# 14_-CURRENT_METER.net
KiCad netlist of a schematic drawn in Altium Designer
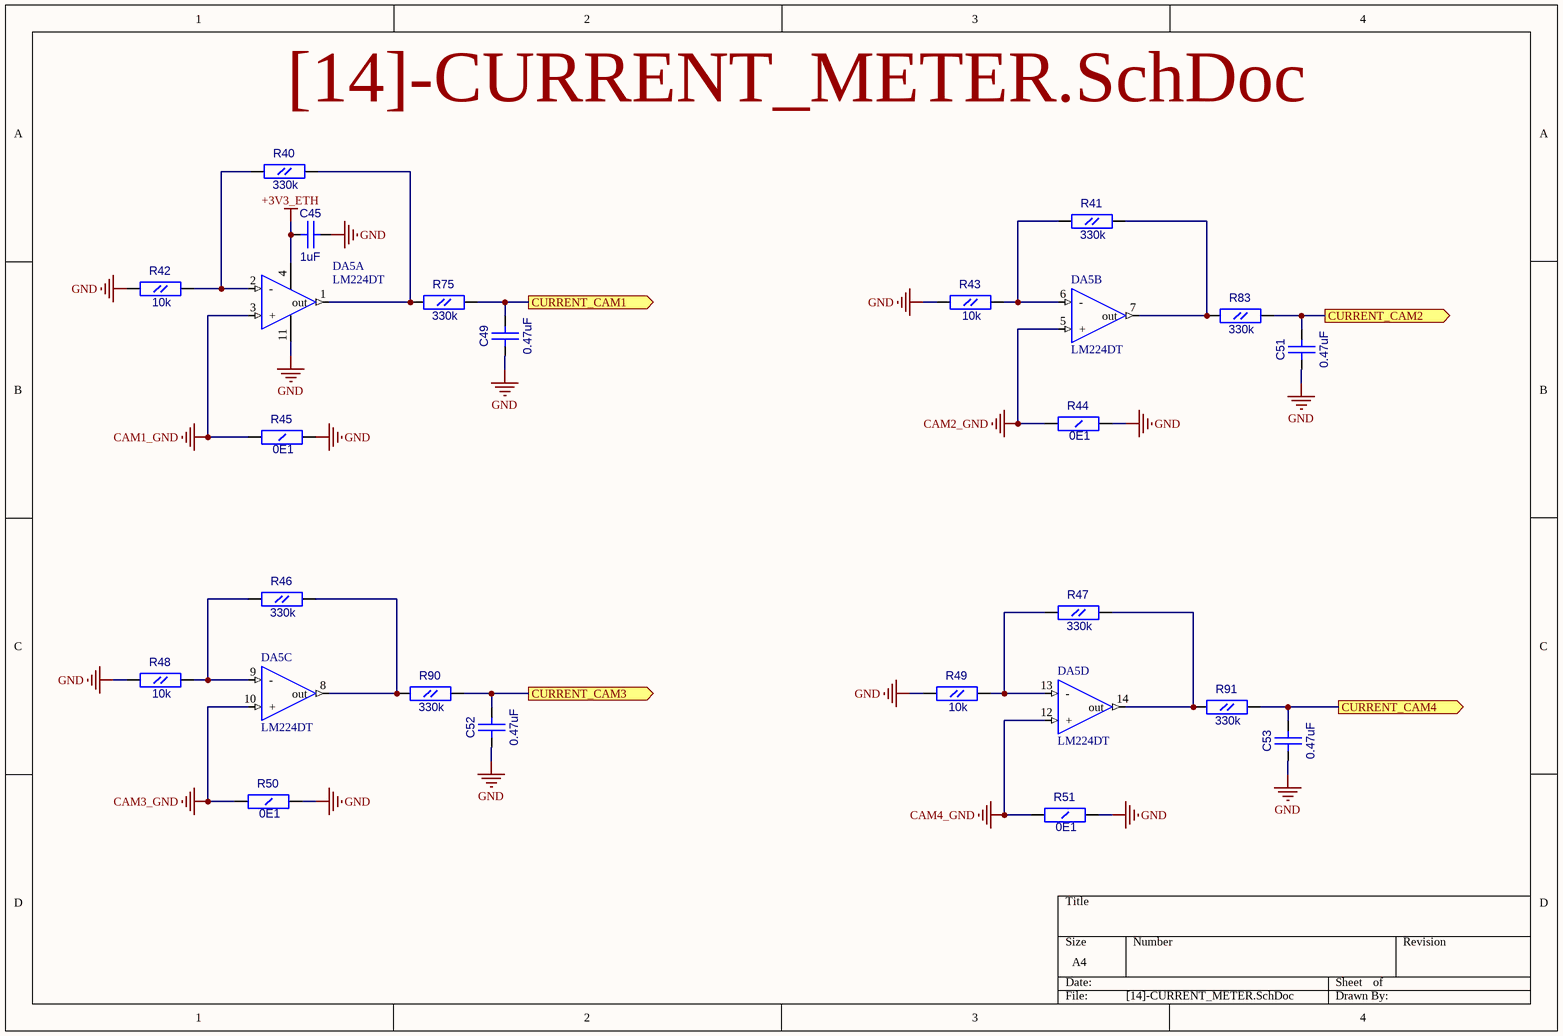
[diagram p0: [14]-CURRENT_METER.SchDoc]

(export (version "E")
  (design (tool "Eeschema 10.0.6"))
  (components
    (comp (ref "C45")
      (value "1uF")
      (footprint "CC0603")
      (description "CC0603")
      (libsource (lib "fizik_lib") (part "CC0603"))
    )
    (comp (ref "C49")
      (value "0.47uF")
      (footprint "CC0603")
      (description "CC0603")
      (libsource (lib "fizik_lib") (part "CC0603"))
    )
    (comp (ref "C51")
      (value "0.47uF")
      (footprint "CC0603")
      (description "CC0603")
      (libsource (lib "fizik_lib") (part "CC0603"))
    )
    (comp (ref "C52")
      (value "0.47uF")
      (footprint "CC0603")
      (description "CC0603")
      (libsource (lib "fizik_lib") (part "CC0603"))
    )
    (comp (ref "C53")
      (value "0.47uF")
      (footprint "CC0603")
      (description "CC0603")
      (libsource (lib "fizik_lib") (part "CC0603"))
    )
    (comp (ref "DA5") (value "LM224DT") (footprint "SO14") (libsource (lib "fizik_lib") (part "LM324D")))
    (comp (ref "R40")
      (value "330k")
      (footprint "RC0603")
      (description "RC0603")
      (libsource (lib "fizik_lib") (part "RC0603"))
    )
    (comp (ref "R41")
      (value "330k")
      (footprint "RC0603")
      (description "RC0603")
      (libsource (lib "fizik_lib") (part "RC0603"))
    )
    (comp (ref "R42")
      (value "10k")
      (footprint "RC0603")
      (description "RC0603")
      (libsource (lib "fizik_lib") (part "RC0603"))
    )
    (comp (ref "R43")
      (value "10k")
      (footprint "RC0603")
      (description "RC0603")
      (libsource (lib "fizik_lib") (part "RC0603"))
    )
    (comp (ref "R44")
      (value "0E1")
      (footprint "RC1206")
      (description "RC1206")
      (libsource (lib "fizik_lib (1)") (part "RC1206"))
    )
    (comp (ref "R45")
      (value "0E1")
      (footprint "RC1206")
      (description "RC1206")
      (libsource (lib "fizik_lib (1)") (part "RC1206"))
    )
    (comp (ref "R46")
      (value "330k")
      (footprint "RC0603")
      (description "RC0603")
      (libsource (lib "fizik_lib") (part "RC0603"))
    )
    (comp (ref "R47")
      (value "330k")
      (footprint "RC0603")
      (description "RC0603")
      (libsource (lib "fizik_lib") (part "RC0603"))
    )
    (comp (ref "R48")
      (value "10k")
      (footprint "RC0603")
      (description "RC0603")
      (libsource (lib "fizik_lib") (part "RC0603"))
    )
    (comp (ref "R49")
      (value "10k")
      (footprint "RC0603")
      (description "RC0603")
      (libsource (lib "fizik_lib") (part "RC0603"))
    )
    (comp (ref "R50")
      (value "0E1")
      (footprint "RC1206")
      (description "RC1206")
      (libsource (lib "fizik_lib (1)") (part "RC1206"))
    )
    (comp (ref "R51")
      (value "0E1")
      (footprint "RC1206")
      (description "RC1206")
      (libsource (lib "fizik_lib (1)") (part "RC1206"))
    )
    (comp (ref "R75")
      (value "330k")
      (footprint "RC0603")
      (description "RC0603")
      (libsource (lib "fizik_lib") (part "RC0603"))
    )
    (comp (ref "R83")
      (value "330k")
      (footprint "RC0603")
      (description "RC0603")
      (libsource (lib "fizik_lib") (part "RC0603"))
    )
    (comp (ref "R90")
      (value "330k")
      (footprint "RC0603")
      (description "RC0603")
      (libsource (lib "fizik_lib") (part "RC0603"))
    )
    (comp (ref "R91")
      (value "330k")
      (footprint "RC0603")
      (description "RC0603")
      (libsource (lib "fizik_lib") (part "RC0603"))
    )
  )
  (nets
    (net (code "1") (name "+3V3_ETH") (class "Default")
      (node (ref "C45") (pin "1") (pinfunction "A_1") (pintype "passive"))
      (node (ref "DA5") (pin "4") (pinfunction "V+_4") (pintype "passive"))
    )
    (net (code "2") (name "/CURRENT_CAM1") (class "Default")
      (node (ref "C49") (pin "2") (pinfunction "B_2") (pintype "passive"))
      (node (ref "R75") (pin "2") (pinfunction "B_2") (pintype "passive"))
    )
    (net (code "3") (name "/CURRENT_CAM2") (class "Default")
      (node (ref "C51") (pin "2") (pinfunction "B_2") (pintype "passive"))
      (node (ref "R83") (pin "2") (pinfunction "B_2") (pintype "passive"))
    )
    (net (code "4") (name "/CURRENT_CAM3") (class "Default")
      (node (ref "C52") (pin "2") (pinfunction "B_2") (pintype "passive"))
      (node (ref "R90") (pin "2") (pinfunction "B_2") (pintype "passive"))
    )
    (net (code "5") (name "/CURRENT_CAM4") (class "Default")
      (node (ref "C53") (pin "2") (pinfunction "B_2") (pintype "passive"))
      (node (ref "R91") (pin "2") (pinfunction "B_2") (pintype "passive"))
    )
    (net (code "6") (name "CAM1_GND") (class "Default")
      (node (ref "DA5") (pin "3") (pinfunction "+_3") (pintype "input"))
      (node (ref "R45") (pin "1") (pinfunction "A_1") (pintype "passive"))
    )
    (net (code "7") (name "CAM2_GND") (class "Default")
      (node (ref "DA5") (pin "5") (pinfunction "+_5") (pintype "input"))
      (node (ref "R44") (pin "1") (pinfunction "A_1") (pintype "passive"))
    )
    (net (code "8") (name "CAM3_GND") (class "Default")
      (node (ref "DA5") (pin "10") (pinfunction "+_10") (pintype "input"))
      (node (ref "R50") (pin "1") (pinfunction "A_1") (pintype "passive"))
    )
    (net (code "9") (name "CAM4_GND") (class "Default")
      (node (ref "DA5") (pin "12") (pinfunction "+_12") (pintype "input"))
      (node (ref "R51") (pin "1") (pinfunction "A_1") (pintype "passive"))
    )
    (net (code "10") (name "GND") (class "Default")
      (node (ref "C45") (pin "2") (pinfunction "B_2") (pintype "passive"))
      (node (ref "C49") (pin "1") (pinfunction "A_1") (pintype "passive"))
      (node (ref "C51") (pin "1") (pinfunction "A_1") (pintype "passive"))
      (node (ref "C52") (pin "1") (pinfunction "A_1") (pintype "passive"))
      (node (ref "C53") (pin "1") (pinfunction "A_1") (pintype "passive"))
      (node (ref "DA5") (pin "11") (pinfunction "V-_11") (pintype "passive"))
      (node (ref "R42") (pin "1") (pinfunction "A_1") (pintype "passive"))
      (node (ref "R43") (pin "1") (pinfunction "A_1") (pintype "passive"))
      (node (ref "R44") (pin "2") (pinfunction "B_2") (pintype "passive"))
      (node (ref "R45") (pin "2") (pinfunction "B_2") (pintype "passive"))
      (node (ref "R48") (pin "1") (pinfunction "A_1") (pintype "passive"))
      (node (ref "R49") (pin "1") (pinfunction "A_1") (pintype "passive"))
      (node (ref "R50") (pin "2") (pinfunction "B_2") (pintype "passive"))
      (node (ref "R51") (pin "2") (pinfunction "B_2") (pintype "passive"))
    )
    (net (code "11") (name "Net-(DA5A--)") (class "Default")
      (node (ref "DA5") (pin "2") (pinfunction "-_2") (pintype "input"))
      (node (ref "R40") (pin "1") (pinfunction "A_1") (pintype "passive"))
      (node (ref "R42") (pin "2") (pinfunction "B_2") (pintype "passive"))
    )
    (net (code "12") (name "Net-(DA5A-out)") (class "Default")
      (node (ref "DA5") (pin "1") (pinfunction "out_1") (pintype "output"))
      (node (ref "R40") (pin "2") (pinfunction "B_2") (pintype "passive"))
      (node (ref "R75") (pin "1") (pinfunction "A_1") (pintype "passive"))
    )
    (net (code "13") (name "Net-(DA5B--)") (class "Default")
      (node (ref "DA5") (pin "6") (pinfunction "-_6") (pintype "input"))
      (node (ref "R41") (pin "1") (pinfunction "A_1") (pintype "passive"))
      (node (ref "R43") (pin "2") (pinfunction "B_2") (pintype "passive"))
    )
    (net (code "14") (name "Net-(DA5B-out)") (class "Default")
      (node (ref "DA5") (pin "7") (pinfunction "out_7") (pintype "output"))
      (node (ref "R41") (pin "2") (pinfunction "B_2") (pintype "passive"))
      (node (ref "R83") (pin "1") (pinfunction "A_1") (pintype "passive"))
    )
    (net (code "15") (name "Net-(DA5C--)") (class "Default")
      (node (ref "DA5") (pin "9") (pinfunction "-_9") (pintype "input"))
      (node (ref "R46") (pin "1") (pinfunction "A_1") (pintype "passive"))
      (node (ref "R48") (pin "2") (pinfunction "B_2") (pintype "passive"))
    )
    (net (code "16") (name "Net-(DA5C-out)") (class "Default")
      (node (ref "DA5") (pin "8") (pinfunction "out_8") (pintype "output"))
      (node (ref "R46") (pin "2") (pinfunction "B_2") (pintype "passive"))
      (node (ref "R90") (pin "1") (pinfunction "A_1") (pintype "passive"))
    )
    (net (code "17") (name "Net-(DA5D--)") (class "Default")
      (node (ref "DA5") (pin "13") (pinfunction "-_13") (pintype "input"))
      (node (ref "R47") (pin "1") (pinfunction "A_1") (pintype "passive"))
      (node (ref "R49") (pin "2") (pinfunction "B_2") (pintype "passive"))
    )
    (net (code "18") (name "Net-(DA5D-out)") (class "Default")
      (node (ref "DA5") (pin "14") (pinfunction "out_14") (pintype "output"))
      (node (ref "R47") (pin "2") (pinfunction "B_2") (pintype "passive"))
      (node (ref "R91") (pin "1") (pinfunction "A_1") (pintype "passive"))
    )
  )
)
